# 1-Schematic_MiniX.net
KiCad netlist of a schematic drawn in EasyEDA
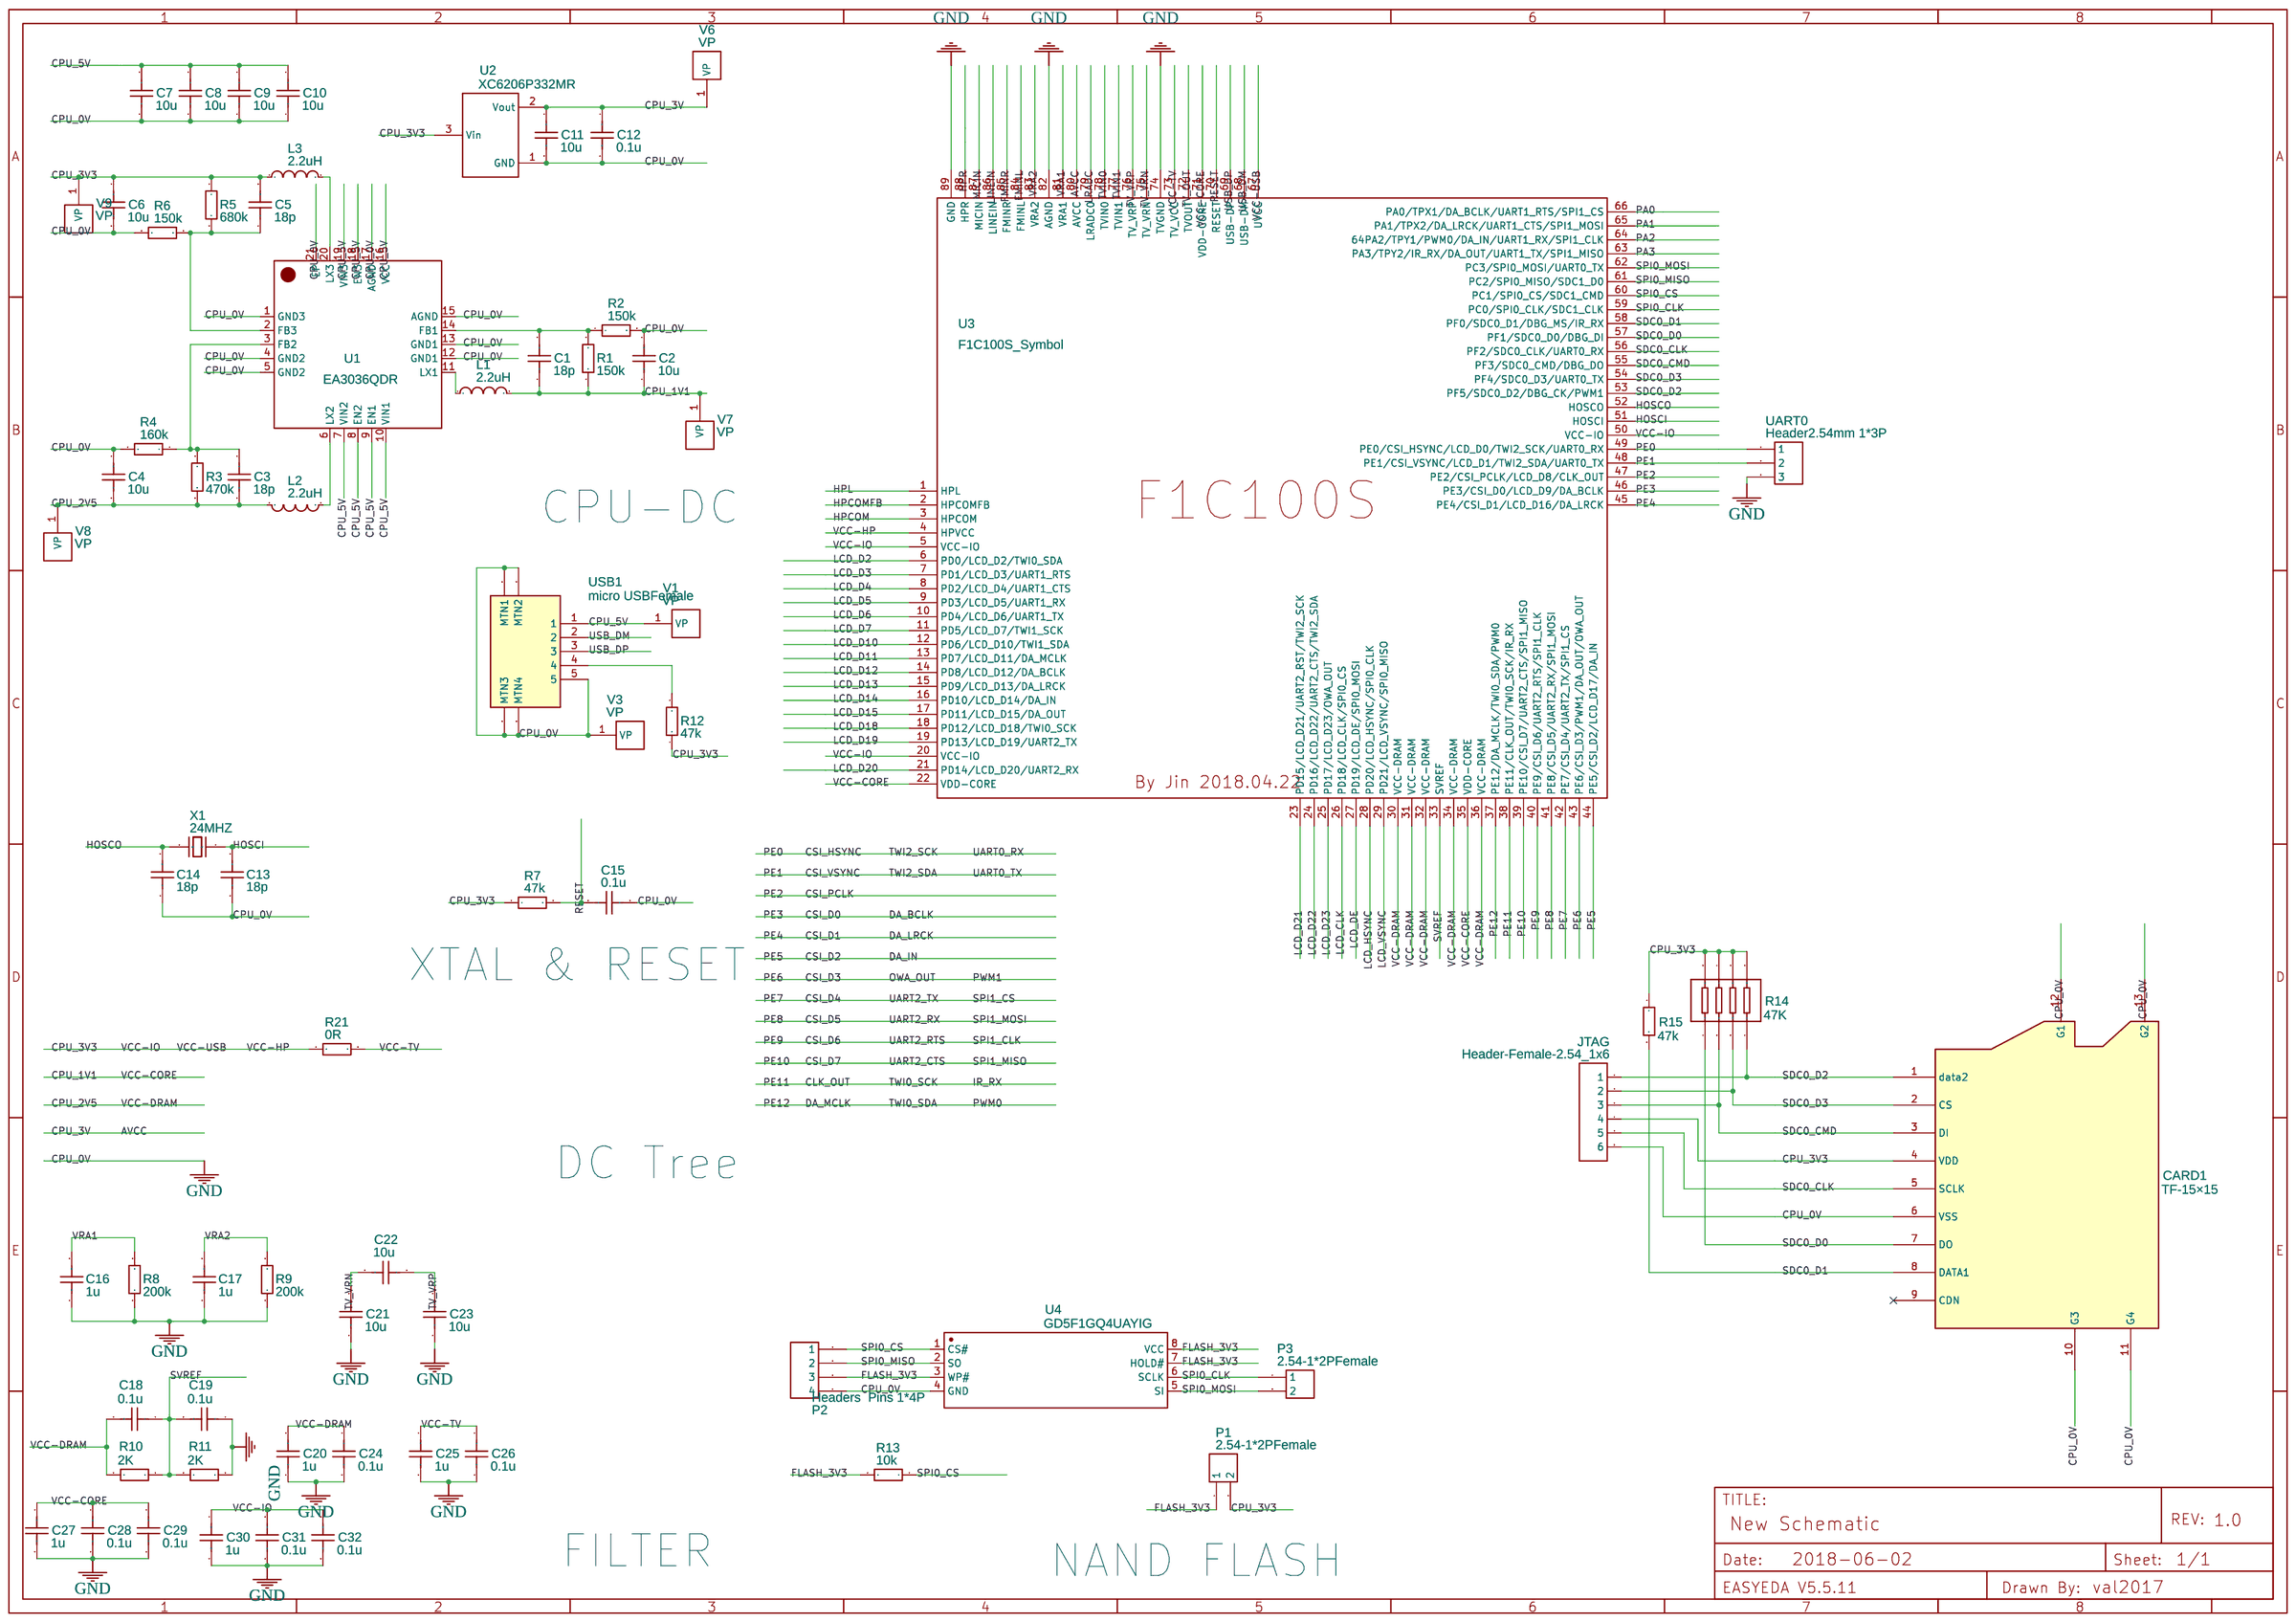
[diagram p0: schematic sheet]

(export (version "E")
  (design (tool "Eeschema 10.0.6"))
  (components
    (comp (ref "C1")
      (value "18p")
      (fields (field (name "BOM_Manufacturer Part") "?"))
      (libsource (lib "") (part "Cap_RAD-0.1_US_1"))
    )
    (comp (ref "C2")
      (value "10u")
      (fields (field (name "BOM_Manufacturer Part") "?"))
      (libsource (lib "") (part "Cap_RAD-0.1_US_1"))
    )
    (comp (ref "C3")
      (value "18p")
      (fields (field (name "BOM_Manufacturer Part") "?"))
      (libsource (lib "") (part "Cap_RAD-0.1_US"))
    )
    (comp (ref "C4")
      (value "10u")
      (fields (field (name "BOM_Manufacturer Part") "?"))
      (libsource (lib "") (part "Cap_RAD-0.1_US"))
    )
    (comp (ref "C5")
      (value "18p")
      (fields (field (name "BOM_Manufacturer Part") "?"))
      (libsource (lib "") (part "Cap_RAD-0.1_US_1"))
    )
    (comp (ref "C6")
      (value "10u")
      (fields (field (name "BOM_Manufacturer Part") "?"))
      (libsource (lib "") (part "Cap_RAD-0.1_US"))
    )
    (comp (ref "C7")
      (value "10u")
      (fields (field (name "BOM_Manufacturer Part") "?"))
      (libsource (lib "") (part "Cap_RAD-0.1_US_1"))
    )
    (comp (ref "C8")
      (value "10u")
      (fields (field (name "BOM_Manufacturer Part") "?"))
      (libsource (lib "") (part "Cap_RAD-0.1_US_1"))
    )
    (comp (ref "C9")
      (value "10u")
      (fields (field (name "BOM_Manufacturer Part") "?"))
      (libsource (lib "") (part "Cap_RAD-0.1_US_1"))
    )
    (comp (ref "C10")
      (value "10u")
      (fields (field (name "BOM_Manufacturer Part") "?"))
      (libsource (lib "") (part "Cap_RAD-0.1_US_1"))
    )
    (comp (ref "C11")
      (value "10u")
      (fields (field (name "BOM_Manufacturer Part") "?"))
      (libsource (lib "") (part "Cap_RAD-0.1_US"))
    )
    (comp (ref "C12")
      (value "0.1u")
      (fields (field (name "BOM_Manufacturer Part") "?"))
      (libsource (lib "") (part "Cap_RAD-0.1_US"))
    )
    (comp (ref "C13")
      (value "18p")
      (fields (field (name "BOM_Manufacturer Part") "?"))
      (libsource (lib "") (part "Cap_RAD-0.1_US_1"))
    )
    (comp (ref "C14")
      (value "18p")
      (fields (field (name "BOM_Manufacturer Part") "?"))
      (libsource (lib "") (part "Cap_RAD-0.1_US_1"))
    )
    (comp (ref "C15")
      (value "0.1u")
      (fields (field (name "BOM_Manufacturer Part") "?"))
      (libsource (lib "") (part "Cap_RAD-0.1_US_2"))
    )
    (comp (ref "C16")
      (value "1u")
      (fields (field (name "BOM_Manufacturer Part") "?"))
      (libsource (lib "") (part "Cap_RAD-0.1_US_1"))
    )
    (comp (ref "C17")
      (value "1u")
      (fields (field (name "BOM_Manufacturer Part") "?"))
      (libsource (lib "") (part "Cap_RAD-0.1_US_1"))
    )
    (comp (ref "C18")
      (value "0.1u")
      (fields (field (name "BOM_Manufacturer Part") "?"))
      (libsource (lib "") (part "Cap_RAD-0.1_US_2"))
    )
    (comp (ref "C19")
      (value "0.1u")
      (fields (field (name "BOM_Manufacturer Part") "?"))
      (libsource (lib "") (part "Cap_RAD-0.1_US_2"))
    )
    (comp (ref "C20")
      (value "1u")
      (fields (field (name "BOM_Manufacturer Part") "?"))
      (libsource (lib "") (part "Cap_RAD-0.1_US"))
    )
    (comp (ref "C21")
      (value "10u")
      (fields (field (name "BOM_Manufacturer Part") "?"))
      (libsource (lib "") (part "Cap_RAD-0.1_US"))
    )
    (comp (ref "C22")
      (value "10u")
      (fields (field (name "BOM_Manufacturer Part") "?"))
      (libsource (lib "") (part "Cap_RAD-0.1_US_2"))
    )
    (comp (ref "C23")
      (value "10u")
      (fields (field (name "BOM_Manufacturer Part") "?"))
      (libsource (lib "") (part "Cap_RAD-0.1_US"))
    )
    (comp (ref "C24")
      (value "0.1u")
      (fields (field (name "BOM_Manufacturer Part") "?"))
      (libsource (lib "") (part "Cap_RAD-0.1_US"))
    )
    (comp (ref "C25")
      (value "1u")
      (fields (field (name "BOM_Manufacturer Part") "?"))
      (libsource (lib "") (part "Cap_RAD-0.1_US"))
    )
    (comp (ref "C26")
      (value "0.1u")
      (fields (field (name "BOM_Manufacturer Part") "?"))
      (libsource (lib "") (part "Cap_RAD-0.1_US"))
    )
    (comp (ref "C27")
      (value "1u")
      (fields (field (name "BOM_Manufacturer Part") "?"))
      (libsource (lib "") (part "Cap_RAD-0.1_US"))
    )
    (comp (ref "C28")
      (value "0.1u")
      (fields (field (name "BOM_Manufacturer Part") "?"))
      (libsource (lib "") (part "Cap_RAD-0.1_US"))
    )
    (comp (ref "C29")
      (value "0.1u")
      (fields (field (name "BOM_Manufacturer Part") "?"))
      (libsource (lib "") (part "Cap_RAD-0.1_US"))
    )
    (comp (ref "C30")
      (value "1u")
      (fields (field (name "BOM_Manufacturer Part") "?"))
      (libsource (lib "") (part "Cap_RAD-0.1_US"))
    )
    (comp (ref "C31")
      (value "0.1u")
      (fields (field (name "BOM_Manufacturer Part") "?"))
      (libsource (lib "") (part "Cap_RAD-0.1_US"))
    )
    (comp (ref "C32")
      (value "0.1u")
      (fields (field (name "BOM_Manufacturer Part") "?"))
      (libsource (lib "") (part "Cap_RAD-0.1_US"))
    )
    (comp (ref "CARD1")
      (value "TF-15×15")
      (fields (field (name "BOM_Supplier Part") "C111196"))
      (libsource (lib "") (part "Unknown_1480_855"))
    )
    (comp (ref "JTAG")
      (value "Header-Female-2.54_1x6")
      (fields
        (field (name "BOM_Manufacturer Part") "Female header 1*6p")
        (field (name "BOM_Supplier Part") "C40877")
      )
      (libsource (lib "") (part "Unknown_1140_790"))
    )
    (comp (ref "L1")
      (value "2.2uH")
      (fields (field (name "BOM_Manufacturer Part") "?"))
      (libsource (lib "") (part "Inductor"))
    )
    (comp (ref "L2")
      (value "2.2uH")
      (fields (field (name "BOM_Manufacturer Part") "?"))
      (libsource (lib "") (part "Inductor_2"))
    )
    (comp (ref "L3")
      (value "2.2uH")
      (fields (field (name "BOM_Manufacturer Part") "?"))
      (libsource (lib "") (part "Inductor_1"))
    )
    (comp (ref "P1")
      (value "2.54-1*2PFemale")
      (fields (field (name "BOM_Supplier Part") "C49661"))
      (libsource (lib "") (part "Unknown_875_1065"))
    )
    (comp (ref "P2")
      (value "Headers  Pins 1*4P")
      (fields (field (name "BOM_Supplier Part") "undefined"))
      (libsource (lib "") (part "Unknown_590_970"))
    )
    (comp (ref "P3")
      (value "2.54-1*2PFemale")
      (fields (field (name "BOM_Supplier Part") "C49661"))
      (libsource (lib "") (part "Unknown_905_990"))
    )
    (comp (ref "R1")
      (value "150k")
      (fields (field (name "BOM_Manufacturer Part") "?"))
      (libsource (lib "") (part "Resistor_2"))
    )
    (comp (ref "R2")
      (value "150k")
      (fields (field (name "BOM_Manufacturer Part") "?"))
      (libsource (lib "") (part "Resistor_1"))
    )
    (comp (ref "R3")
      (value "470k")
      (fields (field (name "BOM_Manufacturer Part") "?"))
      (libsource (lib "") (part "Resistor_3"))
    )
    (comp (ref "R4")
      (value "160k")
      (fields (field (name "BOM_Manufacturer Part") "?"))
      (libsource (lib "") (part "Resistor"))
    )
    (comp (ref "R5")
      (value "680k")
      (fields (field (name "BOM_Manufacturer Part") "?"))
      (libsource (lib "") (part "Resistor_3"))
    )
    (comp (ref "R6")
      (value "150k")
      (fields (field (name "BOM_Manufacturer Part") "?"))
      (libsource (lib "") (part "Resistor"))
    )
    (comp (ref "R7")
      (value "47k")
      (fields (field (name "BOM_Manufacturer Part") "?"))
      (libsource (lib "") (part "Resistor_1"))
    )
    (comp (ref "R8")
      (value "200k")
      (fields (field (name "BOM_Manufacturer Part") "?"))
      (libsource (lib "") (part "Resistor_2"))
    )
    (comp (ref "R9")
      (value "200k")
      (fields (field (name "BOM_Manufacturer Part") "?"))
      (libsource (lib "") (part "Resistor_2"))
    )
    (comp (ref "R10")
      (value "2K")
      (fields (field (name "BOM_Manufacturer Part") "?"))
      (libsource (lib "") (part "Resistor"))
    )
    (comp (ref "R11")
      (value "2K")
      (fields (field (name "BOM_Manufacturer Part") "?"))
      (libsource (lib "") (part "Resistor"))
    )
    (comp (ref "R12")
      (value "47k")
      (fields (field (name "BOM_Manufacturer Part") "?"))
      (libsource (lib "") (part "Resistor_2"))
    )
    (comp (ref "R13")
      (value "10k")
      (fields (field (name "BOM_Manufacturer Part") "?"))
      (libsource (lib "") (part "Resistor"))
    )
    (comp (ref "R14")
      (value "47K")
      (fields
        (field (name "BOM_Manufacturer Part") "4D02WGJ0472TCE")
        (field (name "BOM_Supplier Part") "undefined")
      )
      (libsource (lib "") (part "Unknown_1230_710"))
    )
    (comp (ref "R15")
      (value "47k")
      (fields (field (name "BOM_Manufacturer Part") "?"))
      (libsource (lib "") (part "Resistor_3"))
    )
    (comp (ref "R21")
      (value "0R")
      (fields (field (name "BOM_Manufacturer Part") "?"))
      (libsource (lib "") (part "Resistor_1"))
    )
    (comp (ref "U1")
      (value "EA3036QDR")
      (fields (field (name "BOM_Supplier Part") "C111587"))
      (libsource (lib "") (part "Unknown_210_200"))
    )
    (comp (ref "U2")
      (value "XC6206P332MR")
      (fields (field (name "BOM_Supplier Part") "C5446"))
      (libsource (lib "") (part "Unknown_345_85"))
    )
    (comp (ref "U3")
      (value "F1C100S_Symbol")
      (fields (field (name "BOM_Manufacturer Part") "?"))
      (libsource (lib "") (part "F1C100S_Symbol"))
    )
    (comp (ref "U4")
      (value "GD5F1GQ4UAYIG")
      (fields
        (field (name "BOM_Manufacturer Part") "MX25L12835FM2I-10G")
        (field (name "BOM_Supplier Part") "C71945")
      )
      (libsource (lib "") (part "Unknown_750_950"))
    )
    (comp (ref "UART0")
      (value "Header2.54mm 1*3P")
      (fields (field (name "BOM_Supplier Part") "C49257"))
      (libsource (lib "") (part "Unknown_1260_325"))
    )
    (comp (ref "USB1")
      (value "micro USBFemale")
      (fields (field (name "BOM_Supplier Part") "C10418"))
      (libsource (lib "") (part "Unknown_365_460"))
    )
    (comp (ref "V1")
      (value "VP")
      (fields (field (name "BOM_Manufacturer Part") "?"))
      (libsource (lib "") (part "VP_1"))
    )
    (comp (ref "V3")
      (value "VP")
      (fields (field (name "BOM_Manufacturer Part") "?"))
      (libsource (lib "") (part "VP_1"))
    )
    (comp (ref "V6")
      (value "VP")
      (fields (field (name "BOM_Manufacturer Part") "?"))
      (libsource (lib "") (part "VP_2"))
    )
    (comp (ref "V7")
      (value "VP")
      (fields (field (name "BOM_Manufacturer Part") "?"))
      (libsource (lib "") (part "VP"))
    )
    (comp (ref "V8")
      (value "VP")
      (fields (field (name "BOM_Manufacturer Part") "?"))
      (libsource (lib "") (part "VP"))
    )
    (comp (ref "V9")
      (value "VP")
      (fields (field (name "BOM_Manufacturer Part") "?"))
      (libsource (lib "") (part "VP"))
    )
    (comp (ref "X1")
      (value "24MHZ")
      (fields
        (field (name "BOM_Manufacturer Part") "X49SD12MSD2SC")
        (field (name "BOM_Supplier Part") "undefined")
      )
      (libsource (lib "") (part "Unknown_135_600"))
    )
  )
  (nets
    (net (code "1") (name "/AVCC") (class "Default")
      (node (ref "C11") (pin "1") (pinfunction "1_1") (pintype "unspecified"))
      (node (ref "C12") (pin "1") (pinfunction "1_1") (pintype "unspecified"))
      (node (ref "U2") (pin "2") (pinfunction "Vout_2") (pintype "unspecified"))
      (node (ref "U3") (pin "80") (pinfunction "AVCC_80") (pintype "unspecified"))
      (node (ref "V6") (pin "1") (pinfunction "VP_1") (pintype "unspecified"))
    )
    (net (code "2") (name "/CLK_OUT") (class "Default")
      (node (ref "U3") (pin "38") (pinfunction "PE11/CLK_OUT/TWI0_SCK/IR_RX_38") (pintype "unspecified"))
    )
    (net (code "3") (name "/CPU_1V1") (class "Default")
      (node (ref "C1") (pin "1") (pinfunction "1_1") (pintype "unspecified"))
      (node (ref "C2") (pin "1") (pinfunction "1_1") (pintype "unspecified"))
      (node (ref "C27") (pin "1") (pinfunction "1_1") (pintype "unspecified"))
      (node (ref "C28") (pin "1") (pinfunction "1_1") (pintype "unspecified"))
      (node (ref "C29") (pin "1") (pinfunction "1_1") (pintype "unspecified"))
      (node (ref "L1") (pin "2") (pinfunction "2_2") (pintype "unspecified"))
      (node (ref "R1") (pin "1") (pinfunction "1_1") (pintype "unspecified"))
      (node (ref "U3") (pin "22") (pinfunction "VDD-CORE_22") (pintype "unspecified"))
      (node (ref "U3") (pin "35") (pinfunction "VDD-CORE_35") (pintype "unspecified"))
      (node (ref "U3") (pin "71") (pinfunction "VDD-CORE_71") (pintype "unspecified"))
      (node (ref "V7") (pin "1") (pinfunction "VP_1") (pintype "unspecified"))
    )
    (net (code "4") (name "/CPU_2V5") (class "Default")
      (node (ref "C18") (pin "2") (pinfunction "2_2") (pintype "unspecified"))
      (node (ref "C20") (pin "1") (pinfunction "1_1") (pintype "unspecified"))
      (node (ref "C24") (pin "1") (pinfunction "1_1") (pintype "unspecified"))
      (node (ref "C3") (pin "2") (pinfunction "2_2") (pintype "unspecified"))
      (node (ref "C4") (pin "2") (pinfunction "2_2") (pintype "unspecified"))
      (node (ref "L2") (pin "2") (pinfunction "2_2") (pintype "unspecified"))
      (node (ref "R10") (pin "2") (pinfunction "2_2") (pintype "unspecified"))
      (node (ref "R3") (pin "2") (pinfunction "2_2") (pintype "unspecified"))
      (node (ref "U3") (pin "30") (pinfunction "VCC-DRAM_30") (pintype "unspecified"))
      (node (ref "U3") (pin "31") (pinfunction "VCC-DRAM_31") (pintype "unspecified"))
      (node (ref "U3") (pin "32") (pinfunction "VCC-DRAM_32") (pintype "unspecified"))
      (node (ref "U3") (pin "34") (pinfunction "VCC-DRAM_34") (pintype "unspecified"))
      (node (ref "U3") (pin "36") (pinfunction "VCC-DRAM_36") (pintype "unspecified"))
      (node (ref "V8") (pin "1") (pinfunction "VP_1") (pintype "unspecified"))
    )
    (net (code "5") (name "/CPU_3V3") (class "Default")
      (node (ref "C30") (pin "1") (pinfunction "1_1") (pintype "unspecified"))
      (node (ref "C31") (pin "1") (pinfunction "1_1") (pintype "unspecified"))
      (node (ref "C32") (pin "1") (pinfunction "1_1") (pintype "unspecified"))
      (node (ref "C5") (pin "2") (pinfunction "2_2") (pintype "unspecified"))
      (node (ref "C6") (pin "1") (pinfunction "1_1") (pintype "unspecified"))
      (node (ref "CARD1") (pin "4") (pinfunction "VDD_4") (pintype "input"))
      (node (ref "JTAG") (pin "4") (pinfunction "4_4") (pintype "input"))
      (node (ref "L3") (pin "1") (pinfunction "1_1") (pintype "unspecified"))
      (node (ref "P1") (pin "2") (pinfunction "2_2") (pintype "input"))
      (node (ref "R12") (pin "1") (pinfunction "1_1") (pintype "unspecified"))
      (node (ref "R14") (pin "5") (pinfunction "5_5") (pintype "input"))
      (node (ref "R14") (pin "6") (pinfunction "6_6") (pintype "input"))
      (node (ref "R14") (pin "7") (pinfunction "7_7") (pintype "input"))
      (node (ref "R14") (pin "8") (pinfunction "8_8") (pintype "input"))
      (node (ref "R15") (pin "1") (pinfunction "1_1") (pintype "unspecified"))
      (node (ref "R21") (pin "1") (pinfunction "1_1") (pintype "unspecified"))
      (node (ref "R5") (pin "1") (pinfunction "1_1") (pintype "unspecified"))
      (node (ref "R7") (pin "1") (pinfunction "1_1") (pintype "unspecified"))
      (node (ref "U2") (pin "3") (pinfunction "Vin_3") (pintype "unspecified"))
      (node (ref "U3") (pin "20") (pinfunction "VCC-IO_20") (pintype "unspecified"))
      (node (ref "U3") (pin "4") (pinfunction "HPVCC_4") (pintype "unspecified"))
      (node (ref "U3") (pin "5") (pinfunction "VCC-IO_5") (pintype "unspecified"))
      (node (ref "U3") (pin "50") (pinfunction "VCC-IO_50") (pintype "unspecified"))
      (node (ref "U3") (pin "67") (pinfunction "UVCC_67") (pintype "unspecified"))
      (node (ref "V9") (pin "1") (pinfunction "VP_1") (pintype "unspecified"))
    )
    (net (code "6") (name "/CPU_5V") (class "Default")
      (node (ref "C10") (pin "2") (pinfunction "2_2") (pintype "unspecified"))
      (node (ref "C7") (pin "2") (pinfunction "2_2") (pintype "unspecified"))
      (node (ref "C8") (pin "2") (pinfunction "2_2") (pintype "unspecified"))
      (node (ref "C9") (pin "2") (pinfunction "2_2") (pintype "unspecified"))
      (node (ref "U1") (pin "10") (pinfunction "VIN1_10") (pintype "unspecified"))
      (node (ref "U1") (pin "16") (pinfunction "VCC_16") (pintype "unspecified"))
      (node (ref "U1") (pin "18") (pinfunction "EN3_18") (pintype "unspecified"))
      (node (ref "U1") (pin "19") (pinfunction "VIN3_19") (pintype "unspecified"))
      (node (ref "U1") (pin "7") (pinfunction "VIN2_7") (pintype "unspecified"))
      (node (ref "U1") (pin "8") (pinfunction "EN2_8") (pintype "unspecified"))
      (node (ref "U1") (pin "9") (pinfunction "EN1_9") (pintype "unspecified"))
      (node (ref "USB1") (pin "1") (pinfunction "1_1") (pintype "unspecified"))
      (node (ref "V1") (pin "1") (pinfunction "VP_1") (pintype "unspecified"))
    )
    (net (code "7") (name "/CSI_D0") (class "Default")
      (node (ref "U3") (pin "46") (pinfunction "PE3/CSI_D0/LCD_D9/DA_BCLK_46") (pintype "unspecified"))
    )
    (net (code "8") (name "/CSI_D1") (class "Default")
      (node (ref "U3") (pin "45") (pinfunction "PE4/CSI_D1/LCD_D16/DA_LRCK_45") (pintype "unspecified"))
    )
    (net (code "9") (name "/CSI_D2") (class "Default")
      (node (ref "U3") (pin "44") (pinfunction "PE5/CSI_D2/LCD_D17/DA_IN_44") (pintype "unspecified"))
    )
    (net (code "10") (name "/CSI_D3") (class "Default")
      (node (ref "U3") (pin "43") (pinfunction "PE6/CSI_D3/PWM1/DA_OUT/OWA_OUT_43") (pintype "unspecified"))
    )
    (net (code "11") (name "/CSI_D4") (class "Default")
      (node (ref "U3") (pin "42") (pinfunction "PE7/CSI_D4/UART2_TX/SPI1_CS_42") (pintype "unspecified"))
    )
    (net (code "12") (name "/CSI_D5") (class "Default")
      (node (ref "U3") (pin "41") (pinfunction "PE8/CSI_D5/UART2_RX/SPI1_MOSI_41") (pintype "unspecified"))
    )
    (net (code "13") (name "/CSI_D6") (class "Default")
      (node (ref "U3") (pin "40") (pinfunction "PE9/CSI_D6/UART2_RTS/SPI1_CLK_40") (pintype "unspecified"))
    )
    (net (code "14") (name "/CSI_D7") (class "Default")
      (node (ref "U3") (pin "39") (pinfunction "PE10/CSI_D7/UART2_CTS/SPI1_MISO_39") (pintype "unspecified"))
    )
    (net (code "15") (name "/CSI_HSYNC") (class "Default")
      (node (ref "U3") (pin "49") (pinfunction "PE0/CSI_HSYNC/LCD_D0/TWI2_SCK/UART0_RX_49") (pintype "unspecified"))
      (node (ref "UART0") (pin "1") (pinfunction "1_1") (pintype "input"))
    )
    (net (code "16") (name "/CSI_PCLK") (class "Default")
      (node (ref "U3") (pin "47") (pinfunction "PE2/CSI_PCLK/LCD_D8/CLK_OUT_47") (pintype "unspecified"))
    )
    (net (code "17") (name "/CSI_VSYNC") (class "Default")
      (node (ref "U3") (pin "48") (pinfunction "PE1/CSI_VSYNC/LCD_D1/TWI2_SDA/UART0_TX_48") (pintype "unspecified"))
      (node (ref "UART0") (pin "2") (pinfunction "2_2") (pintype "input"))
    )
    (net (code "18") (name "/DA_MCLK") (class "Default")
      (node (ref "U3") (pin "37") (pinfunction "PE12/DA_MCLK/TWI0_SDA/PWM0_37") (pintype "unspecified"))
    )
    (net (code "19") (name "/FLASH_3V3") (class "Default")
      (node (ref "P1") (pin "1") (pinfunction "1_1") (pintype "input"))
      (node (ref "P2") (pin "3") (pinfunction "3_3") (pintype "input"))
      (node (ref "R13") (pin "2") (pinfunction "2_2") (pintype "unspecified"))
      (node (ref "U4") (pin "3") (pinfunction "WP#_3") (pintype "unspecified"))
      (node (ref "U4") (pin "7") (pinfunction "HOLD#_7") (pintype "unspecified"))
      (node (ref "U4") (pin "8") (pinfunction "VCC_8") (pintype "unspecified"))
    )
    (net (code "20") (name "/FMINL") (class "Default")
      (node (ref "U3") (pin "84") (pinfunction "FMINL_84") (pintype "unspecified"))
    )
    (net (code "21") (name "/FMINR") (class "Default")
      (node (ref "U3") (pin "85") (pinfunction "FMINR_85") (pintype "unspecified"))
    )
    (net (code "22") (name "/HOSCI") (class "Default")
      (node (ref "C13") (pin "2") (pinfunction "2_2") (pintype "unspecified"))
      (node (ref "U3") (pin "51") (pinfunction "HOSCI_51") (pintype "unspecified"))
      (node (ref "X1") (pin "1") (pinfunction "OSC1_1") (pintype "input"))
    )
    (net (code "23") (name "/HOSCO") (class "Default")
      (node (ref "C14") (pin "2") (pinfunction "2_2") (pintype "unspecified"))
      (node (ref "U3") (pin "52") (pinfunction "HOSCO_52") (pintype "unspecified"))
      (node (ref "X1") (pin "2") (pinfunction "OSC2_2") (pintype "input"))
    )
    (net (code "24") (name "/HPCOM") (class "Default")
      (node (ref "U3") (pin "3") (pinfunction "HPCOM_3") (pintype "unspecified"))
    )
    (net (code "25") (name "/HPCOMFB") (class "Default")
      (node (ref "U3") (pin "2") (pinfunction "HPCOMFB_2") (pintype "unspecified"))
    )
    (net (code "26") (name "/HPL") (class "Default")
      (node (ref "U3") (pin "1") (pinfunction "HPL_1") (pintype "unspecified"))
    )
    (net (code "27") (name "/HPR") (class "Default")
      (node (ref "U3") (pin "88") (pinfunction "HPR_88") (pintype "unspecified"))
    )
    (net (code "28") (name "/LCD_CLK") (class "Default")
      (node (ref "U3") (pin "26") (pinfunction "PD18/LCD_CLK/SPI0_CS_26") (pintype "unspecified"))
    )
    (net (code "29") (name "/LCD_D2") (class "Default")
      (node (ref "U3") (pin "6") (pinfunction "PD0/LCD_D2/TWI0_SDA_6") (pintype "unspecified"))
    )
    (net (code "30") (name "/LCD_D3") (class "Default")
      (node (ref "U3") (pin "7") (pinfunction "PD1/LCD_D3/UART1_RTS_7") (pintype "unspecified"))
    )
    (net (code "31") (name "/LCD_D4") (class "Default")
      (node (ref "U3") (pin "8") (pinfunction "PD2/LCD_D4/UART1_CTS_8") (pintype "unspecified"))
    )
    (net (code "32") (name "/LCD_D5") (class "Default")
      (node (ref "U3") (pin "9") (pinfunction "PD3/LCD_D5/UART1_RX_9") (pintype "unspecified"))
    )
    (net (code "33") (name "/LCD_D6") (class "Default")
      (node (ref "U3") (pin "10") (pinfunction "PD4/LCD_D6/UART1_TX_10") (pintype "unspecified"))
    )
    (net (code "34") (name "/LCD_D7") (class "Default")
      (node (ref "U3") (pin "11") (pinfunction "PD5/LCD_D7/TWI1_SCK_11") (pintype "unspecified"))
    )
    (net (code "35") (name "/LCD_D10") (class "Default")
      (node (ref "U3") (pin "12") (pinfunction "PD6/LCD_D10/TWI1_SDA_12") (pintype "unspecified"))
    )
    (net (code "36") (name "/LCD_D11") (class "Default")
      (node (ref "U3") (pin "13") (pinfunction "PD7/LCD_D11/DA_MCLK_13") (pintype "unspecified"))
    )
    (net (code "37") (name "/LCD_D12") (class "Default")
      (node (ref "U3") (pin "14") (pinfunction "PD8/LCD_D12/DA_BCLK_14") (pintype "unspecified"))
    )
    (net (code "38") (name "/LCD_D13") (class "Default")
      (node (ref "U3") (pin "15") (pinfunction "PD9/LCD_D13/DA_LRCK_15") (pintype "unspecified"))
    )
    (net (code "39") (name "/LCD_D14") (class "Default")
      (node (ref "U3") (pin "16") (pinfunction "PD10/LCD_D14/DA_IN_16") (pintype "unspecified"))
    )
    (net (code "40") (name "/LCD_D15") (class "Default")
      (node (ref "U3") (pin "17") (pinfunction "PD11/LCD_D15/DA_OUT_17") (pintype "unspecified"))
    )
    (net (code "41") (name "/LCD_D18") (class "Default")
      (node (ref "U3") (pin "18") (pinfunction "PD12/LCD_D18/TWI0_SCK_18") (pintype "unspecified"))
    )
    (net (code "42") (name "/LCD_D19") (class "Default")
      (node (ref "U3") (pin "19") (pinfunction "PD13/LCD_D19/UART2_TX_19") (pintype "unspecified"))
    )
    (net (code "43") (name "/LCD_D20") (class "Default")
      (node (ref "U3") (pin "21") (pinfunction "PD14/LCD_D20/UART2_RX_21") (pintype "unspecified"))
    )
    (net (code "44") (name "/LCD_D21") (class "Default")
      (node (ref "U3") (pin "23") (pinfunction "PD15/LCD_D21/UART2_RST/TWI2_SCK_23") (pintype "unspecified"))
    )
    (net (code "45") (name "/LCD_D22") (class "Default")
      (node (ref "U3") (pin "24") (pinfunction "PD16/LCD_D22/UART2_CTS/TWI2_SDA_24") (pintype "unspecified"))
    )
    (net (code "46") (name "/LCD_D23") (class "Default")
      (node (ref "U3") (pin "25") (pinfunction "PD17/LCD_D23/OWA_OUT_25") (pintype "unspecified"))
    )
    (net (code "47") (name "/LCD_DE") (class "Default")
      (node (ref "U3") (pin "27") (pinfunction "PD19/LCD_DE/SPI0_MOSI_27") (pintype "unspecified"))
    )
    (net (code "48") (name "/LCD_HSYNC") (class "Default")
      (node (ref "U3") (pin "28") (pinfunction "PD20/LCD_HSYNC/SPI0_CLK_28") (pintype "unspecified"))
    )
    (net (code "49") (name "/LCD_VSYNC") (class "Default")
      (node (ref "U3") (pin "29") (pinfunction "PD21/LCD_VSYNC/SPI0_MISO_29") (pintype "unspecified"))
    )
    (net (code "50") (name "/LINEIN") (class "Default")
      (node (ref "U3") (pin "86") (pinfunction "LINEIN_86") (pintype "unspecified"))
    )
    (net (code "51") (name "/LRADC") (class "Default")
      (node (ref "U3") (pin "79") (pinfunction "LRADC0_79") (pintype "unspecified"))
    )
    (net (code "52") (name "/MICIN") (class "Default")
      (node (ref "U3") (pin "87") (pinfunction "MICIN_87") (pintype "unspecified"))
    )
    (net (code "53") (name "/PA0") (class "Default")
      (node (ref "U3") (pin "66") (pinfunction "PA0/TPX1/DA_BCLK/UART1_RTS/SPI1_CS_66") (pintype "unspecified"))
    )
    (net (code "54") (name "/PA1") (class "Default")
      (node (ref "U3") (pin "65") (pinfunction "PA1/TPX2/DA_LRCK/UART1_CTS/SPI1_MOSI_65") (pintype "unspecified"))
    )
    (net (code "55") (name "/PA2") (class "Default")
      (node (ref "U3") (pin "64") (pinfunction "64PA2/TPY1/PWM0/DA_IN/UART1_RX/SPI1_CLK_64") (pintype "unspecified"))
    )
    (net (code "56") (name "/PA3") (class "Default")
      (node (ref "U3") (pin "63") (pinfunction "PA3/TPY2/IR_RX/DA_OUT/UART1_TX/SPI1_MISO_63") (pintype "unspecified"))
    )
    (net (code "57") (name "/RESET") (class "Default")
      (node (ref "C15") (pin "2") (pinfunction "2_2") (pintype "unspecified"))
      (node (ref "R7") (pin "2") (pinfunction "2_2") (pintype "unspecified"))
      (node (ref "U3") (pin "70") (pinfunction "RESET_70") (pintype "unspecified"))
    )
    (net (code "58") (name "/SDC0_CLK") (class "Default")
      (node (ref "CARD1") (pin "5") (pinfunction "SCLK_5") (pintype "input"))
      (node (ref "JTAG") (pin "5") (pinfunction "5_5") (pintype "input"))
      (node (ref "U3") (pin "56") (pinfunction "PF2/SDC0_CLK/UART0_RX_56") (pintype "unspecified"))
    )
    (net (code "59") (name "/SDC0_CMD") (class "Default")
      (node (ref "CARD1") (pin "3") (pinfunction "DI_3") (pintype "input"))
      (node (ref "JTAG") (pin "3") (pinfunction "3_3") (pintype "input"))
      (node (ref "R14") (pin "2") (pinfunction "2_2") (pintype "input"))
      (node (ref "U3") (pin "55") (pinfunction "PF3/SDC0_CMD/DBG_DO_55") (pintype "unspecified"))
    )
    (net (code "60") (name "/SDC0_D0") (class "Default")
      (node (ref "CARD1") (pin "7") (pinfunction "DO_7") (pintype "input"))
      (node (ref "R14") (pin "1") (pinfunction "1_1") (pintype "input"))
      (node (ref "U3") (pin "57") (pinfunction "PF1/SDC0_D0/DBG_DI_57") (pintype "unspecified"))
    )
    (net (code "61") (name "/SDC0_D1") (class "Default")
      (node (ref "CARD1") (pin "8") (pinfunction "DATA1_8") (pintype "input"))
      (node (ref "R15") (pin "2") (pinfunction "2_2") (pintype "unspecified"))
      (node (ref "U3") (pin "58") (pinfunction "PF0/SDC0_D1/DBG_MS/IR_RX_58") (pintype "unspecified"))
    )
    (net (code "62") (name "/SDC0_D2") (class "Default")
      (node (ref "CARD1") (pin "1") (pinfunction "data2_1") (pintype "input"))
      (node (ref "JTAG") (pin "1") (pinfunction "1_1") (pintype "input"))
      (node (ref "R14") (pin "4") (pinfunction "4_4") (pintype "input"))
      (node (ref "U3") (pin "53") (pinfunction "PF5/SDC0_D2/DBG_CK/PWM1_53") (pintype "unspecified"))
    )
    (net (code "63") (name "/SDC0_D3") (class "Default")
      (node (ref "CARD1") (pin "2") (pinfunction "CS_2") (pintype "input"))
      (node (ref "JTAG") (pin "2") (pinfunction "2_2") (pintype "input"))
      (node (ref "R14") (pin "3") (pinfunction "3_3") (pintype "input"))
      (node (ref "U3") (pin "54") (pinfunction "PF4/SDC0_D3/UART0_TX_54") (pintype "unspecified"))
    )
    (net (code "64") (name "/SPI0_CLK") (class "Default")
      (node (ref "P3") (pin "1") (pinfunction "1_1") (pintype "input"))
      (node (ref "U3") (pin "59") (pinfunction "PC0/SPI0_CLK/SDC1_CLK_59") (pintype "unspecified"))
      (node (ref "U4") (pin "6") (pinfunction "SCLK_6") (pintype "unspecified"))
    )
    (net (code "65") (name "/SPI0_CS") (class "Default")
      (node (ref "P2") (pin "1") (pinfunction "1_1") (pintype "input"))
      (node (ref "R13") (pin "1") (pinfunction "1_1") (pintype "unspecified"))
      (node (ref "U3") (pin "60") (pinfunction "PC1/SPI0_CS/SDC1_CMD_60") (pintype "unspecified"))
      (node (ref "U4") (pin "1") (pinfunction "CS#_1") (pintype "unspecified"))
    )
    (net (code "66") (name "/SPI0_MISO") (class "Default")
      (node (ref "P2") (pin "2") (pinfunction "2_2") (pintype "input"))
      (node (ref "U3") (pin "61") (pinfunction "PC2/SPI0_MISO/SDC1_D0_61") (pintype "unspecified"))
      (node (ref "U4") (pin "2") (pinfunction "SO_2") (pintype "unspecified"))
    )
    (net (code "67") (name "/SPI0_MOSI") (class "Default")
      (node (ref "P3") (pin "2") (pinfunction "2_2") (pintype "input"))
      (node (ref "U3") (pin "62") (pinfunction "PC3/SPI0_MOSI/UART0_TX_62") (pintype "unspecified"))
      (node (ref "U4") (pin "5") (pinfunction "SI_5") (pintype "unspecified"))
    )
    (net (code "68") (name "/SVREF") (class "Default")
      (node (ref "C18") (pin "1") (pinfunction "1_1") (pintype "unspecified"))
      (node (ref "C19") (pin "2") (pinfunction "2_2") (pintype "unspecified"))
      (node (ref "R10") (pin "1") (pinfunction "1_1") (pintype "unspecified"))
      (node (ref "R11") (pin "2") (pinfunction "2_2") (pintype "unspecified"))
      (node (ref "U3") (pin "33") (pinfunction "SVREF_33") (pintype "unspecified"))
    )
    (net (code "69") (name "/TVIN0") (class "Default")
      (node (ref "U3") (pin "78") (pinfunction "TVIN0_78") (pintype "unspecified"))
    )
    (net (code "70") (name "/TVIN1") (class "Default")
      (node (ref "U3") (pin "77") (pinfunction "TVIN1_77") (pintype "unspecified"))
    )
    (net (code "71") (name "/TV_OUT") (class "Default")
      (node (ref "U3") (pin "72") (pinfunction "TVOUT_72") (pintype "unspecified"))
    )
    (net (code "72") (name "/TV_VRN") (class "Default")
      (node (ref "C21") (pin "1") (pinfunction "1_1") (pintype "unspecified"))
      (node (ref "C22") (pin "2") (pinfunction "2_2") (pintype "unspecified"))
      (node (ref "U3") (pin "75") (pinfunction "TV_VRN_75") (pintype "unspecified"))
    )
    (net (code "73") (name "/TV_VRP") (class "Default")
      (node (ref "C22") (pin "1") (pinfunction "1_1") (pintype "unspecified"))
      (node (ref "C23") (pin "1") (pinfunction "1_1") (pintype "unspecified"))
      (node (ref "U3") (pin "76") (pinfunction "TV_VRP_76") (pintype "unspecified"))
    )
    (net (code "74") (name "/USB_DM") (class "Default")
      (node (ref "U3") (pin "68") (pinfunction "USB-DM_68") (pintype "unspecified"))
      (node (ref "USB1") (pin "2") (pinfunction "2_2") (pintype "unspecified"))
    )
    (net (code "75") (name "/USB_DP") (class "Default")
      (node (ref "U3") (pin "69") (pinfunction "USB-DP_69") (pintype "unspecified"))
      (node (ref "USB1") (pin "3") (pinfunction "3_3") (pintype "unspecified"))
    )
    (net (code "76") (name "/VCC-TV") (class "Default")
      (node (ref "C25") (pin "1") (pinfunction "1_1") (pintype "unspecified"))
      (node (ref "C26") (pin "1") (pinfunction "1_1") (pintype "unspecified"))
      (node (ref "R21") (pin "2") (pinfunction "2_2") (pintype "unspecified"))
      (node (ref "U3") (pin "73") (pinfunction "TV_VCC_73") (pintype "unspecified"))
    )
    (net (code "77") (name "/VRA1") (class "Default")
      (node (ref "C16") (pin "2") (pinfunction "2_2") (pintype "unspecified"))
      (node (ref "R8") (pin "2") (pinfunction "2_2") (pintype "unspecified"))
      (node (ref "U3") (pin "81") (pinfunction "VRA1_81") (pintype "unspecified"))
    )
    (net (code "78") (name "/VRA2") (class "Default")
      (node (ref "C17") (pin "2") (pinfunction "2_2") (pintype "unspecified"))
      (node (ref "R9") (pin "2") (pinfunction "2_2") (pintype "unspecified"))
      (node (ref "U3") (pin "83") (pinfunction "VRA2_83") (pintype "unspecified"))
    )
    (net (code "79") (name "GND") (class "Default")
      (node (ref "C10") (pin "1") (pinfunction "1_1") (pintype "unspecified"))
      (node (ref "C11") (pin "2") (pinfunction "2_2") (pintype "unspecified"))
      (node (ref "C12") (pin "2") (pinfunction "2_2") (pintype "unspecified"))
      (node (ref "C13") (pin "1") (pinfunction "1_1") (pintype "unspecified"))
      (node (ref "C14") (pin "1") (pinfunction "1_1") (pintype "unspecified"))
      (node (ref "C15") (pin "1") (pinfunction "1_1") (pintype "unspecified"))
      (node (ref "C16") (pin "1") (pinfunction "1_1") (pintype "unspecified"))
      (node (ref "C17") (pin "1") (pinfunction "1_1") (pintype "unspecified"))
      (node (ref "C19") (pin "1") (pinfunction "1_1") (pintype "unspecified"))
      (node (ref "C2") (pin "2") (pinfunction "2_2") (pintype "unspecified"))
      (node (ref "C20") (pin "2") (pinfunction "2_2") (pintype "unspecified"))
      (node (ref "C21") (pin "2") (pinfunction "2_2") (pintype "unspecified"))
      (node (ref "C23") (pin "2") (pinfunction "2_2") (pintype "unspecified"))
      (node (ref "C24") (pin "2") (pinfunction "2_2") (pintype "unspecified"))
      (node (ref "C25") (pin "2") (pinfunction "2_2") (pintype "unspecified"))
      (node (ref "C26") (pin "2") (pinfunction "2_2") (pintype "unspecified"))
      (node (ref "C27") (pin "2") (pinfunction "2_2") (pintype "unspecified"))
      (node (ref "C28") (pin "2") (pinfunction "2_2") (pintype "unspecified"))
      (node (ref "C29") (pin "2") (pinfunction "2_2") (pintype "unspecified"))
      (node (ref "C30") (pin "2") (pinfunction "2_2") (pintype "unspecified"))
      (node (ref "C31") (pin "2") (pinfunction "2_2") (pintype "unspecified"))
      (node (ref "C32") (pin "2") (pinfunction "2_2") (pintype "unspecified"))
      (node (ref "C4") (pin "1") (pinfunction "1_1") (pintype "unspecified"))
      (node (ref "C6") (pin "2") (pinfunction "2_2") (pintype "unspecified"))
      (node (ref "C7") (pin "1") (pinfunction "1_1") (pintype "unspecified"))
      (node (ref "C8") (pin "1") (pinfunction "1_1") (pintype "unspecified"))
      (node (ref "C9") (pin "1") (pinfunction "1_1") (pintype "unspecified"))
      (node (ref "CARD1") (pin "10") (pinfunction "G3_10") (pintype "input"))
      (node (ref "CARD1") (pin "11") (pinfunction "G4_11") (pintype "input"))
      (node (ref "CARD1") (pin "12") (pinfunction "G1_12") (pintype "input"))
      (node (ref "CARD1") (pin "13") (pinfunction "G2_13") (pintype "input"))
      (node (ref "CARD1") (pin "6") (pinfunction "VSS_6") (pintype "input"))
      (node (ref "JTAG") (pin "6") (pinfunction "6_6") (pintype "input"))
      (node (ref "P2") (pin "4") (pinfunction "4_4") (pintype "input"))
      (node (ref "R11") (pin "1") (pinfunction "1_1") (pintype "unspecified"))
      (node (ref "R2") (pin "2") (pinfunction "2_2") (pintype "unspecified"))
      (node (ref "R4") (pin "2") (pinfunction "2_2") (pintype "unspecified"))
      (node (ref "R6") (pin "2") (pinfunction "2_2") (pintype "unspecified"))
      (node (ref "R8") (pin "1") (pinfunction "1_1") (pintype "unspecified"))
      (node (ref "R9") (pin "1") (pinfunction "1_1") (pintype "unspecified"))
      (node (ref "U1") (pin "1") (pinfunction "GND3_1") (pintype "unspecified"))
      (node (ref "U1") (pin "12") (pinfunction "GND1_12") (pintype "unspecified"))
      (node (ref "U1") (pin "13") (pinfunction "GND1_13") (pintype "unspecified"))
      (node (ref "U1") (pin "15") (pinfunction "AGND_15") (pintype "unspecified"))
      (node (ref "U1") (pin "17") (pinfunction "AGND_17") (pintype "unspecified"))
      (node (ref "U1") (pin "21") (pinfunction "EP_21") (pintype "unspecified"))
      (node (ref "U1") (pin "4") (pinfunction "GND2_4") (pintype "unspecified"))
      (node (ref "U1") (pin "5") (pinfunction "GND2_5") (pintype "unspecified"))
      (node (ref "U2") (pin "1") (pinfunction "GND_1") (pintype "unspecified"))
      (node (ref "U3") (pin "74") (pinfunction "TVGND_74") (pintype "unspecified"))
      (node (ref "U3") (pin "82") (pinfunction "AGND_82") (pintype "unspecified"))
      (node (ref "U3") (pin "89") (pinfunction "GND_89") (pintype "unspecified"))
      (node (ref "U4") (pin "4") (pinfunction "GND_4") (pintype "unspecified"))
      (node (ref "UART0") (pin "3") (pinfunction "3_3") (pintype "input"))
      (node (ref "USB1") (pin "0") (pinfunction "MTN1_0") (pintype "input"))
      (node (ref "USB1") (pin "5") (pinfunction "5_5") (pintype "unspecified"))
      (node (ref "V3") (pin "1") (pinfunction "VP_1") (pintype "unspecified"))
    )
    (net (code "80") (name "Net-(R12-Pad2)") (class "Default")
      (node (ref "R12") (pin "2") (pinfunction "2_2") (pintype "unspecified"))
      (node (ref "USB1") (pin "4") (pinfunction "4_4") (pintype "unspecified"))
    )
    (net (code "81") (name "Net-(U1-FB1)") (class "Default")
      (node (ref "C1") (pin "2") (pinfunction "2_2") (pintype "unspecified"))
      (node (ref "R1") (pin "2") (pinfunction "2_2") (pintype "unspecified"))
      (node (ref "R2") (pin "1") (pinfunction "1_1") (pintype "unspecified"))
      (node (ref "U1") (pin "14") (pinfunction "FB1_14") (pintype "unspecified"))
    )
    (net (code "82") (name "Net-(U1-FB2)") (class "Default")
      (node (ref "C3") (pin "1") (pinfunction "1_1") (pintype "unspecified"))
      (node (ref "R3") (pin "1") (pinfunction "1_1") (pintype "unspecified"))
      (node (ref "R4") (pin "1") (pinfunction "1_1") (pintype "unspecified"))
      (node (ref "U1") (pin "3") (pinfunction "FB2_3") (pintype "unspecified"))
    )
    (net (code "83") (name "Net-(U1-FB3)") (class "Default")
      (node (ref "C5") (pin "1") (pinfunction "1_1") (pintype "unspecified"))
      (node (ref "R5") (pin "2") (pinfunction "2_2") (pintype "unspecified"))
      (node (ref "R6") (pin "1") (pinfunction "1_1") (pintype "unspecified"))
      (node (ref "U1") (pin "2") (pinfunction "FB3_2") (pintype "unspecified"))
    )
    (net (code "84") (name "Net-(U1-LX1)") (class "Default")
      (node (ref "L1") (pin "1") (pinfunction "1_1") (pintype "unspecified"))
      (node (ref "U1") (pin "11") (pinfunction "LX1_11") (pintype "unspecified"))
    )
    (net (code "85") (name "Net-(U1-LX2)") (class "Default")
      (node (ref "L2") (pin "1") (pinfunction "1_1") (pintype "unspecified"))
      (node (ref "U1") (pin "6") (pinfunction "LX2_6") (pintype "unspecified"))
    )
    (net (code "86") (name "Net-(U1-LX3)") (class "Default")
      (node (ref "L3") (pin "2") (pinfunction "2_2") (pintype "unspecified"))
      (node (ref "U1") (pin "20") (pinfunction "LX3_20") (pintype "unspecified"))
    )
    (net (code "87") (name "unconnected-(CARD1-CDN-Pad9)") (class "Default")
      (node (ref "CARD1") (pin "9") (pinfunction "CDN_9") (pintype "input+no_connect"))
    )
  )
)
